# CAN.net
KiCad netlist of a schematic drawn in Altium Designer
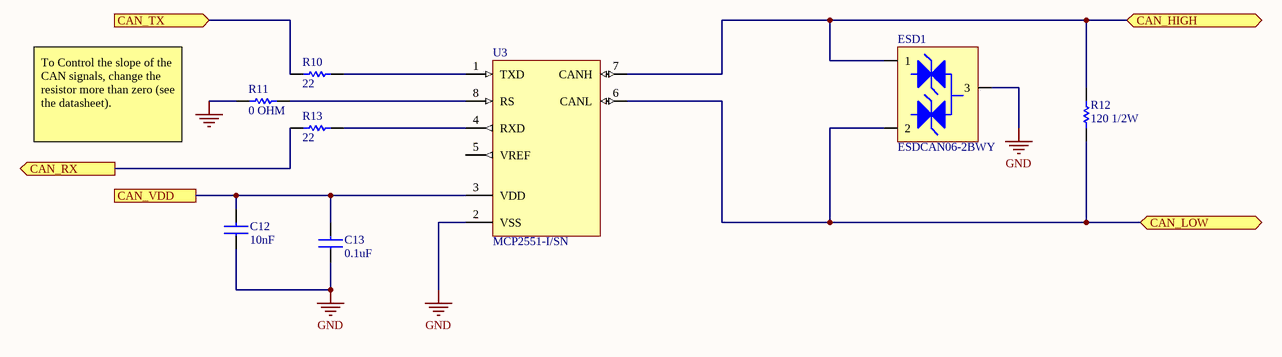
[diagram p0: CAN.SchDoc]

(export (version "E")
  (design (tool "Eeschema 10.0.6"))
  (components
    (comp (ref "C12")
      (value "10nF")
      (footprint "C0805")
      (fields
        (field (name "MANUFACTURER") "Yageo")
        (field (name "MANUFACTURER PART NUMBER") "CC0805KRX7R9BB103")
        (field (name "TOLERANCE") "10%")
      )
      (libsource (lib "MCx") (part "CC0805KRX7R9BB103"))
    )
    (comp (ref "C13")
      (value "0.1uF")
      (footprint "C0805")
      (description "Cap Ceramic 0.1uF 50V X7R 10% SMD 2.0 x 1.2 mm 125 C Paper T/R")
      (fields
        (field (name "MANUFACTURER") "KEMET")
        (field (name "MANUFACTURER PART NUMBER") "C0805C104K5RACTU")
      )
      (libsource (lib "MCx") (part "C0805C104K5RACTU"))
    )
    (comp (ref "ESD1")
      (value "ESDCAN06-2BWY")
      (footprint "MC1:SOT65P210X110-3N")
      (description "TVS DIODE 35V 59V SOT323-3")
      (fields (field (name "MANUFACTURER") "STMicroelectronics"))
      (libsource (lib "MC1") (part "ESDCAN06-2BWY"))
    )
    (comp (ref "R10")
      (value "22")
      (footprint "R0805")
      (description "Resistor;  Thick Film;  22 Ohms;  0.125 W;  5%;  SMT;  0805;  TCR 73 ppm/DegC;  Cut Tape")
      (fields
        (field (name "MANUFACTURER") "Vishay Dale")
        (field (name "MANUFACTURER PART NUMBER") "CRCW080522R0JNEA")
      )
      (libsource (lib "MCx") (part "CRCW080522R0JNEA"))
    )
    (comp (ref "R11")
      (value "0 OHM")
      (footprint "R0805")
      (description "Res Thick Film 0805 0 Ohm Pad SMD Automotive T/R")
      (fields
        (field (name "MANUFACTURER") "KOA Speer")
        (field (name "MANUFACTURER PART NUMBER") "RK73Z2ATTD")
      )
      (libsource (lib "MCx") (part "RK73Z2ATTD"))
    )
    (comp (ref "R12")
      (value "120 1/2W")
      (footprint "MC1:RESC3225X60X45NL20T20")
      (description "Thick Film Resistors - SMD 1/2watt 120ohms 1%")
      (fields
        (field (name "MANUFACTURER") "Vishay")
        (field (name "MANUFACTURER PART NUMBER") "CRCW1210120RFKEA")
      )
      (libsource (lib "MC1") (part "CRCW1210120RFKEA"))
    )
    (comp (ref "R13")
      (value "22")
      (footprint "R0805")
      (description "Resistor;  Thick Film;  22 Ohms;  0.125 W;  5%;  SMT;  0805;  TCR 73 ppm/DegC;  Cut Tape")
      (fields
        (field (name "MANUFACTURER") "Vishay Dale")
        (field (name "MANUFACTURER PART NUMBER") "CRCW080522R0JNEA")
      )
      (libsource (lib "MCx") (part "CRCW080522R0JNEA"))
    )
    (comp (ref "U3")
      (value "MCP2551-I/SN")
      (footprint "MC1:SOIC-SN8_N")
      (description "IC TRANSCEIVER CAN HI-SPD 8-SOIC")
      (fields (field (name "MANUFACTURER") "Microchip"))
      (libsource (lib "MC1") (part "MCP2551-I/SN"))
    )
  )
  (nets
    (net (code "1") (name "/CAN_HIGH") (class "Default")
      (node (ref "ESD1") (pin "1") (pinfunction "1_1") (pintype "passive"))
      (node (ref "R12") (pin "2") (pinfunction "2_2") (pintype "passive"))
      (node (ref "U3") (pin "7") (pinfunction "CANH_7") (pintype "bidirectional"))
    )
    (net (code "2") (name "/CAN_LOW") (class "Default")
      (node (ref "ESD1") (pin "2") (pinfunction "2_2") (pintype "passive"))
      (node (ref "R12") (pin "1") (pinfunction "1_1") (pintype "passive"))
      (node (ref "U3") (pin "6") (pinfunction "CANL_6") (pintype "bidirectional"))
    )
    (net (code "3") (name "/CAN_RX") (class "Default")
      (node (ref "R13") (pin "1") (pinfunction "1_1") (pintype "passive"))
    )
    (net (code "4") (name "/CAN_TX") (class "Default")
      (node (ref "R10") (pin "1") (pinfunction "1_1") (pintype "passive"))
    )
    (net (code "5") (name "/CAN_VDD") (class "Default")
      (node (ref "C12") (pin "2") (pinfunction "2_2") (pintype "passive"))
      (node (ref "C13") (pin "2") (pinfunction "2_2") (pintype "passive"))
      (node (ref "U3") (pin "3") (pinfunction "VDD_3") (pintype "power_in"))
    )
    (net (code "6") (name "GND") (class "Default")
      (node (ref "C12") (pin "1") (pinfunction "1_1") (pintype "passive"))
      (node (ref "C13") (pin "1") (pinfunction "1_1") (pintype "passive"))
      (node (ref "ESD1") (pin "3") (pinfunction "3_3") (pintype "passive"))
      (node (ref "R11") (pin "1") (pinfunction "1_1") (pintype "passive"))
      (node (ref "U3") (pin "2") (pinfunction "VSS_2") (pintype "power_in"))
    )
    (net (code "7") (name "Net-(U3-RS)") (class "Default")
      (node (ref "R11") (pin "2") (pinfunction "2_2") (pintype "passive"))
      (node (ref "U3") (pin "8") (pinfunction "RS_8") (pintype "input"))
    )
    (net (code "8") (name "Net-(U3-RXD)") (class "Default")
      (node (ref "R13") (pin "2") (pinfunction "2_2") (pintype "passive"))
      (node (ref "U3") (pin "4") (pinfunction "RXD_4") (pintype "output"))
    )
    (net (code "9") (name "Net-(U3-TXD)") (class "Default")
      (node (ref "R10") (pin "2") (pinfunction "2_2") (pintype "passive"))
      (node (ref "U3") (pin "1") (pinfunction "TXD_1") (pintype "input"))
    )
    (net (code "10") (name "unconnected-(U3-VREF-Pad5)") (class "Default")
      (node (ref "U3") (pin "5") (pinfunction "VREF_5") (pintype "output"))
    )
  )
)
